# Sheet1.net
KiCad netlist of a schematic drawn in Altium Designer
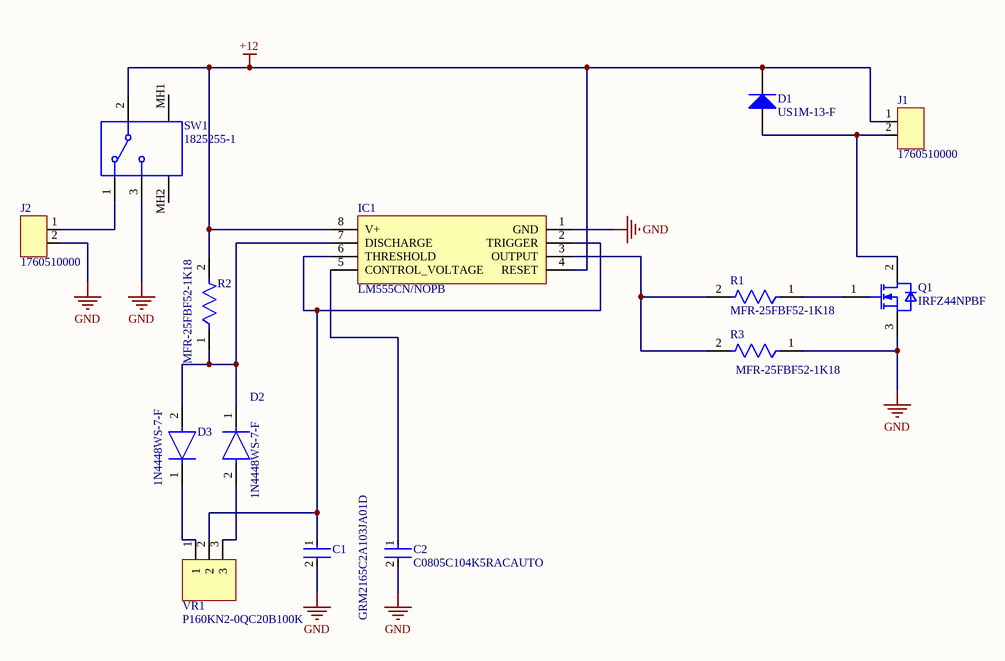
[diagram p0: Sheet1.SchDoc]

(export (version "E")
  (design (tool "Eeschema 10.0.6"))
  (components
    (comp (ref "C1")
      (value "GRM2165C2A103JA01D")
      (footprint "FP-GRM216-0_1-0_05-IPC_C")
      (description "Chip Multilayer Ceramic Capacitors for General Purpose, 0805, 10000pF, C0G, 30ppm/°C, 5%, 100V")
      (libsource (lib "Altium Content Vault") (part "b4654b650e69147ec39a6b967a45e02"))
    )
    (comp (ref "C2")
      (value "C0805C104K5RACAUTO")
      (footprint "FP-C0805C-DN-MFG")
      (description "CAP CER 0.1UF 50V X7R 0805")
      (fields (field (name "MANUFACTURER") "KEMET") (field (name "TOLERANCE") "0.1"))
      (libsource (lib "Altium Content Vault") (part "b4654b650e69147ec39a6b967a45e02"))
    )
    (comp (ref "D1")
      (value "US1M-13-F")
      (footprint "DIOD-SMA-2_A_V")
      (description "Ultra-Fast Rectifier, 1 A, 1.7 V, -65 to 150 degC, 2-Pin SMA, RoHS, Tape and Reel")
      (fields (field (name "MANUFACTURER") "Diodes Inc"))
      (libsource (lib "Altium Content Vault") (part "D-AK-2"))
    )
    (comp (ref "D2")
      (value "1N4448WS-7-F")
      (footprint "FP-SOD323-MFG")
      (description "DIODE GEN PURP 75V 250MA SOD323")
      (fields
        (field (name "MANUFACTURER") "Diodes Incorporated")
        (field (name "OCTOPART") "https://octopart.com/1n4448ws-7-f-diodes+inc.-55389585")
      )
      (libsource (lib "Altium Content Vault") (part "d7152d700b627762746794eb795d46e"))
    )
    (comp (ref "D3")
      (value "1N4448WS-7-F")
      (footprint "FP-SOD323-MFG")
      (description "DIODE GEN PURP 75V 250MA SOD323")
      (fields
        (field (name "MANUFACTURER") "Diodes Incorporated")
        (field (name "OCTOPART") "https://octopart.com/1n4448ws-7-f-diodes+inc.-55389585")
      )
      (libsource (lib "Altium Content Vault") (part "d7152d700b627762746794eb795d46e"))
    )
    (comp (ref "IC1")
      (value "LM555CN/NOPB")
      (footprint "DIP794W45P254L959H508Q8")
      (description "IC OSC SINGLE TIMER 100KHZ 8-DIP \"555 Type, Timer/Oscillator (Single) IC 100kHz 8-PDIP\"")
      (fields (field (name "MANUFACTURER") "Texas Instruments"))
      (libsource (lib "Schlib2") (part "LM555CN/NOPB"))
    )
    (comp (ref "J1")
      (value "1760510000")
      (footprint "1760490000")
      (description "Weidmuller PCB Terminal Block PM Series, 2-Ch, 5.08mm Pitch, TH, Screw Termination, Black")
      (fields (field (name "MANUFACTURER") "Weidmuller") (field (name "VOLTAGE") "300V"))
      (libsource (lib "Schlib2") (part "1760510000"))
    )
    (comp (ref "J2")
      (value "1760510000")
      (footprint "1760490000")
      (description "Weidmuller PCB Terminal Block PM Series, 2-Ch, 5.08mm Pitch, TH, Screw Termination, Black")
      (fields (field (name "MANUFACTURER") "Weidmuller") (field (name "VOLTAGE") "300V"))
      (libsource (lib "") (part "1760510000_1"))
    )
    (comp (ref "Q1")
      (value "IRFZ44NPBF")
      (footprint "IFX-PG-TO220-3-904-1")
      (description "MOSFET, Power; N-Ch; VDSS 55V; RDS(ON) 17.5 Milliohms; ID 49A; TO-220AB; PD 94W; -55deg")
      (fields (field (name "MANUFACTURER") "Infineon"))
      (libsource (lib "Schlib2") (part "IRFZ44NPBF"))
    )
    (comp (ref "R1")
      (value "MFR-25FBF52-1K18")
      (footprint "FP-MFR-25-MFG")
      (description "1.18 kOhms ±1% 0.25W, 1/4W Through Hole Resistor Axial  Metal Film")
      (fields (field (name "MANUFACTURER") "Yageo"))
      (libsource (lib "Altium Content Vault") (part "1029c3af85768c4190bb7ad29bc67b5"))
    )
    (comp (ref "R2")
      (value "MFR-25FBF52-1K18")
      (footprint "FP-MFR-25-MFG")
      (description "1.18 kOhms ±1% 0.25W, 1/4W Through Hole Resistor Axial  Metal Film")
      (fields (field (name "MANUFACTURER") "Yageo"))
      (libsource (lib "Altium Content Vault") (part "1029c3af85768c4190bb7ad29bc67b5"))
    )
    (comp (ref "R3")
      (value "MFR-25FBF52-1K18")
      (footprint "FP-MFR-25-MFG")
      (description "1.18 kOhms ±1% 0.25W, 1/4W Through Hole Resistor Axial  Metal Film")
      (fields (field (name "MANUFACTURER") "Yageo"))
      (libsource (lib "Altium Content Vault") (part "1029c3af85768c4190bb7ad29bc67b5"))
    )
    (comp (ref "SW1")
      (value "1825255-1")
      (footprint "TECO-1825255-1_V")
      (description "Slide Switch, SPDT, 125 V, -20 to 85 degC, 5-Pin THD, RoHS, Tray")
      (fields (field (name "MANUFACTURER") "TE Connectivity"))
      (libsource (lib "Altium Content Vault") (part "SW-SPDT-3_C"))
    )
    (comp (ref "VR1")
      (value "P160KN2-0QC20B100K")
      (footprint "IC3_P160KN2-0QC20B100K_BIT")
      (description "Potentiometer, Conductive Plastic, 0.2W, 100000ohm, 20% +/-Tol, 1 Turn(s)")
      (fields (field (name "MANUFACTURER") "TT Electronics") (field (name "TOLERANCE") "20%"))
      (libsource (lib "Schlib2") (part "P160KN2-0QC20B100K"))
    )
  )
  (nets
    (net (code "1") (name "+12") (class "Default")
      (node (ref "D1") (pin "2") (pinfunction "K_2") (pintype "passive"))
      (node (ref "IC1") (pin "4") (pinfunction "RESET_4") (pintype "passive"))
      (node (ref "IC1") (pin "8") (pinfunction "V+_8") (pintype "power_in"))
      (node (ref "J1") (pin "1") (pinfunction "1_1") (pintype "passive"))
      (node (ref "R2") (pin "2") (pinfunction "2_2") (pintype "passive"))
      (node (ref "SW1") (pin "2") (pinfunction "2_2") (pintype "passive"))
    )
    (net (code "2") (name "GND") (class "Default")
      (node (ref "C1") (pin "2") (pinfunction "2_2") (pintype "passive"))
      (node (ref "C2") (pin "2") (pinfunction "2_2") (pintype "passive"))
      (node (ref "IC1") (pin "1") (pinfunction "GND_1") (pintype "power_in"))
      (node (ref "J2") (pin "2") (pinfunction "2_2") (pintype "passive"))
      (node (ref "Q1") (pin "3") (pinfunction "SOURCE_3") (pintype "passive"))
      (node (ref "R3") (pin "1") (pinfunction "1_1") (pintype "passive"))
      (node (ref "SW1") (pin "3") (pinfunction "3_3") (pintype "passive"))
    )
    (net (code "3") (name "Net-(D1-A)") (class "Default")
      (node (ref "D1") (pin "1") (pinfunction "A_1") (pintype "passive"))
      (node (ref "J1") (pin "2") (pinfunction "2_2") (pintype "passive"))
      (node (ref "Q1") (pin "2") (pinfunction "DRAIN_2") (pintype "passive"))
    )
    (net (code "4") (name "Net-(D2-A)") (class "Default")
      (node (ref "D2") (pin "2") (pinfunction "A_2") (pintype "passive"))
      (node (ref "VR1") (pin "3") (pinfunction "3_3") (pintype "passive"))
    )
    (net (code "5") (name "Net-(D2-C)") (class "Default")
      (node (ref "D2") (pin "1") (pinfunction "C_1") (pintype "passive"))
      (node (ref "D3") (pin "2") (pinfunction "A_2") (pintype "passive"))
      (node (ref "IC1") (pin "7") (pinfunction "DISCHARGE_7") (pintype "passive"))
      (node (ref "R2") (pin "1") (pinfunction "1_1") (pintype "passive"))
    )
    (net (code "6") (name "Net-(D3-C)") (class "Default")
      (node (ref "D3") (pin "1") (pinfunction "C_1") (pintype "passive"))
      (node (ref "VR1") (pin "1") (pinfunction "1_1") (pintype "passive"))
    )
    (net (code "7") (name "Net-(IC1-CONTROL_VOLTAGE)") (class "Default")
      (node (ref "C2") (pin "1") (pinfunction "1_1") (pintype "passive"))
      (node (ref "IC1") (pin "5") (pinfunction "CONTROL_VOLTAGE_5") (pintype "passive"))
    )
    (net (code "8") (name "Net-(IC1-OUTPUT)") (class "Default")
      (node (ref "IC1") (pin "3") (pinfunction "OUTPUT_3") (pintype "passive"))
      (node (ref "R1") (pin "2") (pinfunction "2_2") (pintype "passive"))
      (node (ref "R3") (pin "2") (pinfunction "2_2") (pintype "passive"))
    )
    (net (code "9") (name "Net-(IC1-THRESHOLD)") (class "Default")
      (node (ref "C1") (pin "1") (pinfunction "1_1") (pintype "passive"))
      (node (ref "IC1") (pin "2") (pinfunction "TRIGGER_2") (pintype "passive"))
      (node (ref "IC1") (pin "6") (pinfunction "THRESHOLD_6") (pintype "passive"))
      (node (ref "VR1") (pin "2") (pinfunction "2_2") (pintype "passive"))
    )
    (net (code "10") (name "Net-(J2-Pad1)") (class "Default")
      (node (ref "J2") (pin "1") (pinfunction "1_1") (pintype "passive"))
      (node (ref "SW1") (pin "1") (pinfunction "1_1") (pintype "passive"))
    )
    (net (code "11") (name "Net-(Q1-GATE)") (class "Default")
      (node (ref "Q1") (pin "1") (pinfunction "GATE_1") (pintype "passive"))
      (node (ref "R1") (pin "1") (pinfunction "1_1") (pintype "passive"))
    )
    (net (code "12") (name "unconnected-(SW1-PadMH1)") (class "Default")
      (node (ref "SW1") (pin "MH1") (pinfunction "MH1_MH1") (pintype "passive"))
    )
    (net (code "13") (name "unconnected-(SW1-PadMH2)") (class "Default")
      (node (ref "SW1") (pin "MH2") (pinfunction "MH2_MH2") (pintype "passive"))
    )
  )
)
